# advanced.net
KiCad netlist of a schematic drawn in EAGLE
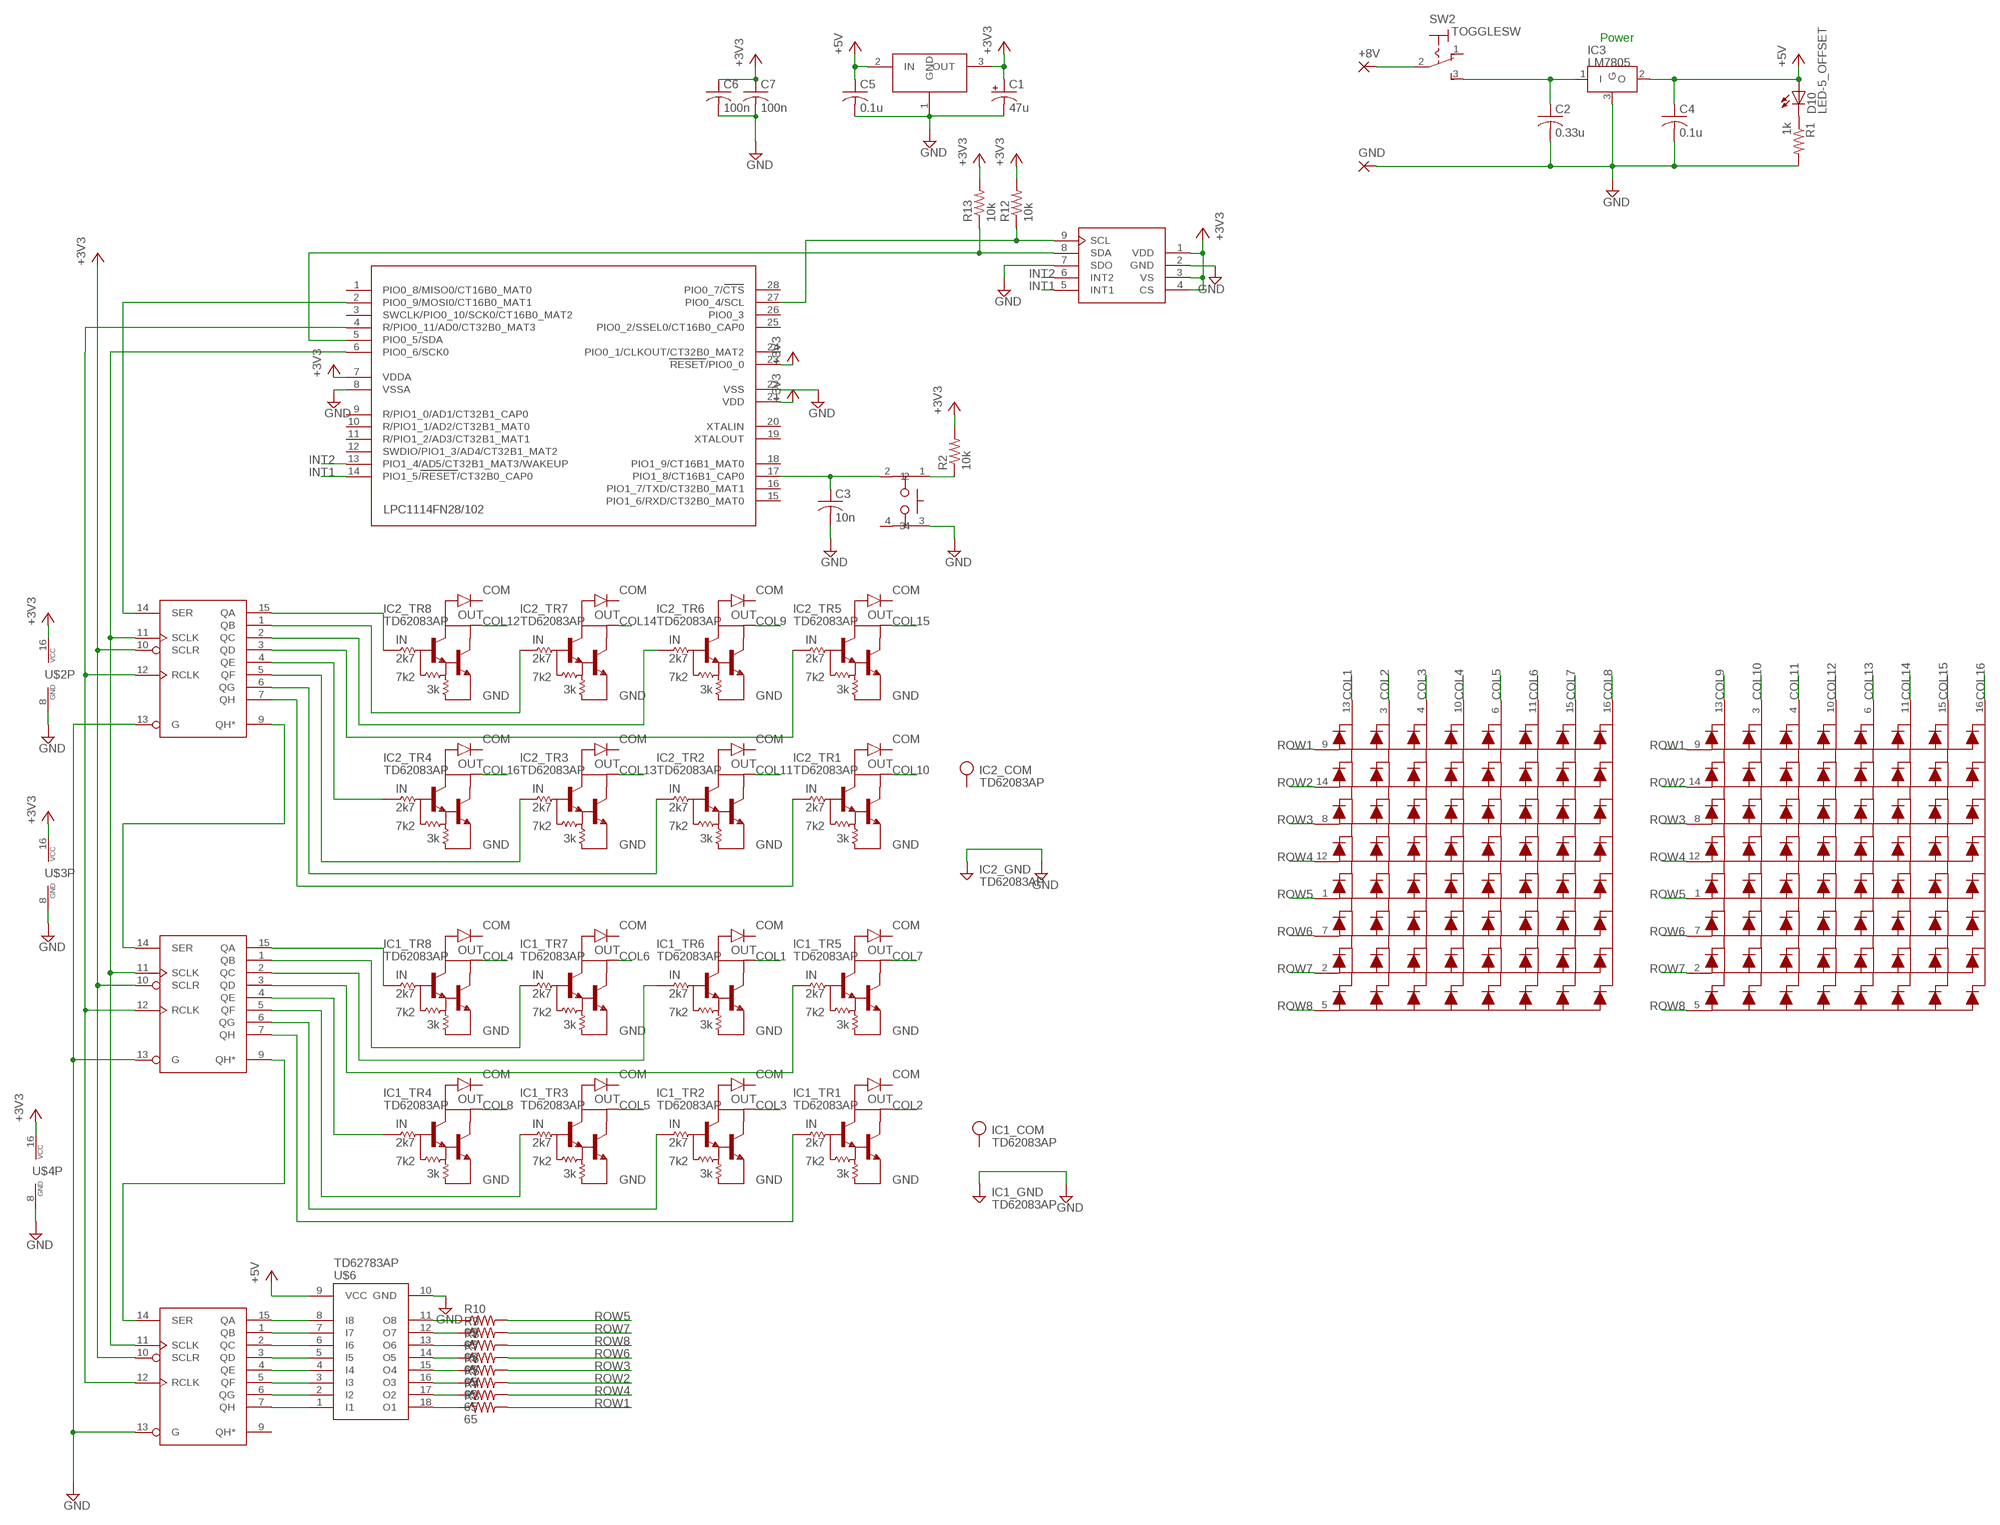
[diagram p0: schematic, sheet 1]

(export (version "E")
  (design (tool "Eeschema 10.0.6"))
  (components
    (comp (ref "+8V")
      (value "POWERPAD-2.0")
      (footprint "eagle-import:POWERPAD-2.0")
      (libsource (lib "eagle-import") (part "POWERPAD-2.0"))
    )
    (comp (ref "C1")
      (value "47u")
      (footprint "eagle-import:E2,5-5")
      (libsource (lib "eagle-import") (part "CC-2.5-5"))
    )
    (comp (ref "C2")
      (value "0.33u")
      (footprint "eagle-import:C025-024X044")
      (libsource (lib "eagle-import") (part "C/2.5"))
    )
    (comp (ref "C3")
      (value "10n")
      (footprint "eagle-import:C025-024X044")
      (libsource (lib "eagle-import") (part "C/2.5"))
    )
    (comp (ref "C4")
      (value "0.1u")
      (footprint "eagle-import:C025-024X044")
      (libsource (lib "eagle-import") (part "C/2.5"))
    )
    (comp (ref "C5")
      (value "0.1u")
      (footprint "eagle-import:C025-024X044")
      (libsource (lib "eagle-import") (part "C/2.5"))
    )
    (comp (ref "C6")
      (value "100n")
      (footprint "eagle-import:C025-024X044")
      (libsource (lib "eagle-import") (part "C/2.5"))
    )
    (comp (ref "C7")
      (value "100n")
      (footprint "eagle-import:C025-024X044")
      (libsource (lib "eagle-import") (part "C/2.5"))
    )
    (comp (ref "D1")
      (value "OSL641505-BX")
      (footprint "eagle-import:OSL641505-XX")
      (libsource (lib "eagle-import") (part "OSL641505-BX"))
    )
    (comp (ref "D10")
      (value "LED-5_OFFSET")
      (footprint "eagle-import:LED5_OFFSET")
      (libsource (lib "eagle-import") (part "LED-5_OFFSET"))
    )
    (comp (ref "DELDEL")
      (value "OSL641505-BX")
      (footprint "eagle-import:OSL641505-XX")
      (libsource (lib "eagle-import") (part "OSL641505-BX"))
    )
    (comp (ref "GND")
      (value "POWERPAD-2.0")
      (footprint "eagle-import:POWERPAD-2.0")
      (libsource (lib "eagle-import") (part "POWERPAD-2.0"))
    )
    (comp (ref "IC1")
      (value "TD62083AP")
      (footprint "eagle-import:DIL18")
      (libsource (lib "eagle-import") (part "TD62083AP"))
    )
    (comp (ref "IC2")
      (value "TD62083AP")
      (footprint "eagle-import:DIL18")
      (libsource (lib "eagle-import") (part "TD62083AP"))
    )
    (comp (ref "IC3")
      (value "LM7805")
      (footprint "eagle-import:7805-LARGEHOLE")
      (libsource (lib "eagle-import") (part "78(LARGEHOLE)"))
    )
    (comp (ref "R1")
      (value "1k")
      (footprint "eagle-import:0204_7")
      (libsource (lib "eagle-import") (part "R/7"))
    )
    (comp (ref "R2")
      (value "10k")
      (footprint "eagle-import:0204_7")
      (libsource (lib "eagle-import") (part "R/7"))
    )
    (comp (ref "R3")
      (value "65")
      (footprint "eagle-import:0204_7")
      (libsource (lib "eagle-import") (part "R/7"))
    )
    (comp (ref "R4")
      (value "65")
      (footprint "eagle-import:0204_7")
      (libsource (lib "eagle-import") (part "R/7"))
    )
    (comp (ref "R5")
      (value "65")
      (footprint "eagle-import:0204_7")
      (libsource (lib "eagle-import") (part "R/7"))
    )
    (comp (ref "R6")
      (value "65")
      (footprint "eagle-import:0204_7")
      (libsource (lib "eagle-import") (part "R/7"))
    )
    (comp (ref "R7")
      (value "65")
      (footprint "eagle-import:0204_7")
      (libsource (lib "eagle-import") (part "R/7"))
    )
    (comp (ref "R8")
      (value "65")
      (footprint "eagle-import:0204_7")
      (libsource (lib "eagle-import") (part "R/7"))
    )
    (comp (ref "R9")
      (value "65")
      (footprint "eagle-import:0204_7")
      (libsource (lib "eagle-import") (part "R/7"))
    )
    (comp (ref "R10")
      (value "65")
      (footprint "eagle-import:0204_7")
      (libsource (lib "eagle-import") (part "R/7"))
    )
    (comp (ref "R12")
      (value "10k")
      (footprint "eagle-import:0204_7")
      (libsource (lib "eagle-import") (part "R/7"))
    )
    (comp (ref "R13")
      (value "10k")
      (footprint "eagle-import:0204_7")
      (libsource (lib "eagle-import") (part "R/7"))
    )
    (comp (ref "SW1")
      (value "PUSHSW")
      (footprint "eagle-import:PUSHSW")
      (libsource (lib "eagle-import") (part "PUSHSW"))
    )
    (comp (ref "SW2")
      (value "TOGGLESW")
      (footprint "eagle-import:TOGGLESW")
      (libsource (lib "eagle-import") (part "TOGGLESW"))
    )
    (comp (ref "U$1")
      (value "LPC1114FN28")
      (footprint "eagle-import:DIP28(600MIL)")
      (libsource (lib "eagle-import") (part "LPC1114FN28"))
    )
    (comp (ref "U$2")
      (value "74HC595N")
      (footprint "eagle-import:DIL16")
      (libsource (lib "eagle-import") (part "74595NHC"))
    )
    (comp (ref "U$3")
      (value "74HC595N")
      (footprint "eagle-import:DIL16")
      (libsource (lib "eagle-import") (part "74595NHC"))
    )
    (comp (ref "U$4")
      (value "74HC595N")
      (footprint "eagle-import:DIL16")
      (libsource (lib "eagle-import") (part "74595NHC"))
    )
    (comp (ref "U$5")
      (value "AKI_ADXL345")
      (footprint "eagle-import:AKI_ADXL345")
      (libsource (lib "eagle-import") (part "AKI_ADXL345"))
    )
    (comp (ref "U$6")
      (value "TD62783AP")
      (footprint "eagle-import:DIL18")
      (libsource (lib "eagle-import") (part "TD62783AP"))
    )
    (comp (ref "U$8")
      (value "S-812C3.3AY")
      (footprint "eagle-import:TO92-")
      (libsource (lib "eagle-import") (part "S-812CAY3.3"))
    )
  )
  (nets
    (net (code "1") (name "+3V3") (class "Default")
      (node (ref "C1") (pin "+") (pinfunction "+_+") (pintype "passive"))
      (node (ref "C6") (pin "1") (pinfunction "1_1") (pintype "passive"))
      (node (ref "C7") (pin "1") (pinfunction "1_1") (pintype "passive"))
      (node (ref "R12") (pin "2") (pinfunction "2_2") (pintype "passive"))
      (node (ref "R13") (pin "2") (pinfunction "2_2") (pintype "passive"))
      (node (ref "R2") (pin "2") (pinfunction "2_2") (pintype "passive"))
      (node (ref "U$1") (pin "21") (pinfunction "VDD_21") (pintype "power_in"))
      (node (ref "U$1") (pin "23") (pinfunction "RESET/PIO0_0_23") (pintype "bidirectional"))
      (node (ref "U$1") (pin "7") (pinfunction "VDDA_7") (pintype "power_in"))
      (node (ref "U$2") (pin "10") (pinfunction "SCLR_10") (pintype "input"))
      (node (ref "U$2") (pin "16") (pinfunction "VCC_16") (pintype "power_in"))
      (node (ref "U$3") (pin "10") (pinfunction "SCLR_10") (pintype "input"))
      (node (ref "U$3") (pin "16") (pinfunction "VCC_16") (pintype "power_in"))
      (node (ref "U$4") (pin "10") (pinfunction "SCLR_10") (pintype "input"))
      (node (ref "U$4") (pin "16") (pinfunction "VCC_16") (pintype "power_in"))
      (node (ref "U$5") (pin "1") (pinfunction "VDD_1") (pintype "power_in"))
      (node (ref "U$5") (pin "3") (pinfunction "VS_3") (pintype "power_in"))
      (node (ref "U$5") (pin "4") (pinfunction "CS_4") (pintype "input"))
      (node (ref "U$8") (pin "3") (pinfunction "OUT_3") (pintype "power_in"))
    )
    (net (code "2") (name "+5V") (class "Default")
      (node (ref "C4") (pin "1") (pinfunction "1_1") (pintype "passive"))
      (node (ref "C5") (pin "1") (pinfunction "1_1") (pintype "passive"))
      (node (ref "D10") (pin "A") (pinfunction "A_A") (pintype "passive"))
      (node (ref "IC3") (pin "2") (pinfunction "O_2") (pintype "power_in"))
      (node (ref "U$6") (pin "9") (pinfunction "VCC_9") (pintype "power_in"))
      (node (ref "U$8") (pin "2") (pinfunction "IN_2") (pintype "power_in"))
    )
    (net (code "3") (name "/COL1") (class "Default")
      (node (ref "D1") (pin "13") (pinfunction "P$9_13") (pintype "passive"))
      (node (ref "IC1") (pin "13") (pinfunction "C_13") (pintype "passive"))
    )
    (net (code "4") (name "/COL2") (class "Default")
      (node (ref "D1") (pin "3") (pinfunction "P$10_3") (pintype "passive"))
      (node (ref "IC1") (pin "18") (pinfunction "C_18") (pintype "passive"))
    )
    (net (code "5") (name "/COL3") (class "Default")
      (node (ref "D1") (pin "4") (pinfunction "P$11_4") (pintype "passive"))
      (node (ref "IC1") (pin "17") (pinfunction "C_17") (pintype "passive"))
    )
    (net (code "6") (name "/COL4") (class "Default")
      (node (ref "D1") (pin "10") (pinfunction "P$12_10") (pintype "passive"))
      (node (ref "IC1") (pin "11") (pinfunction "C_11") (pintype "passive"))
    )
    (net (code "7") (name "/COL5") (class "Default")
      (node (ref "D1") (pin "6") (pinfunction "P$13_6") (pintype "passive"))
      (node (ref "IC1") (pin "16") (pinfunction "C_16") (pintype "passive"))
    )
    (net (code "8") (name "/COL6") (class "Default")
      (node (ref "D1") (pin "11") (pinfunction "P$14_11") (pintype "passive"))
      (node (ref "IC1") (pin "12") (pinfunction "C_12") (pintype "passive"))
    )
    (net (code "9") (name "/COL7") (class "Default")
      (node (ref "D1") (pin "15") (pinfunction "P$15_15") (pintype "passive"))
      (node (ref "IC1") (pin "14") (pinfunction "C_14") (pintype "passive"))
    )
    (net (code "10") (name "/COL8") (class "Default")
      (node (ref "D1") (pin "16") (pinfunction "P$16_16") (pintype "passive"))
      (node (ref "IC1") (pin "15") (pinfunction "C_15") (pintype "passive"))
    )
    (net (code "11") (name "/COL9") (class "Default")
      (node (ref "DELDEL") (pin "13") (pinfunction "P$9_13") (pintype "passive"))
      (node (ref "IC2") (pin "13") (pinfunction "C_13") (pintype "passive"))
    )
    (net (code "12") (name "/COL10") (class "Default")
      (node (ref "DELDEL") (pin "3") (pinfunction "P$10_3") (pintype "passive"))
      (node (ref "IC2") (pin "18") (pinfunction "C_18") (pintype "passive"))
    )
    (net (code "13") (name "/COL11") (class "Default")
      (node (ref "DELDEL") (pin "4") (pinfunction "P$11_4") (pintype "passive"))
      (node (ref "IC2") (pin "17") (pinfunction "C_17") (pintype "passive"))
    )
    (net (code "14") (name "/COL12") (class "Default")
      (node (ref "DELDEL") (pin "10") (pinfunction "P$12_10") (pintype "passive"))
      (node (ref "IC2") (pin "11") (pinfunction "C_11") (pintype "passive"))
    )
    (net (code "15") (name "/COL13") (class "Default")
      (node (ref "DELDEL") (pin "6") (pinfunction "P$13_6") (pintype "passive"))
      (node (ref "IC2") (pin "16") (pinfunction "C_16") (pintype "passive"))
    )
    (net (code "16") (name "/COL14") (class "Default")
      (node (ref "DELDEL") (pin "11") (pinfunction "P$14_11") (pintype "passive"))
      (node (ref "IC2") (pin "12") (pinfunction "C_12") (pintype "passive"))
    )
    (net (code "17") (name "/COL15") (class "Default")
      (node (ref "DELDEL") (pin "15") (pinfunction "P$15_15") (pintype "passive"))
      (node (ref "IC2") (pin "14") (pinfunction "C_14") (pintype "passive"))
    )
    (net (code "18") (name "/COL16") (class "Default")
      (node (ref "DELDEL") (pin "16") (pinfunction "P$16_16") (pintype "passive"))
      (node (ref "IC2") (pin "15") (pinfunction "C_15") (pintype "passive"))
    )
    (net (code "19") (name "/INT1") (class "Default")
      (node (ref "U$1") (pin "14") (pinfunction "PIO1_5/RESET/CT32B0_CAP0_14") (pintype "bidirectional"))
      (node (ref "U$5") (pin "5") (pinfunction "INT1_5") (pintype "output"))
    )
    (net (code "20") (name "/INT2") (class "Default")
      (node (ref "U$1") (pin "13") (pinfunction "PIO1_4/AD5/CT32B1_MAT3/WAKEUP_13") (pintype "bidirectional"))
      (node (ref "U$5") (pin "6") (pinfunction "INT2_6") (pintype "output"))
    )
    (net (code "21") (name "/ROW1") (class "Default")
      (node (ref "D1") (pin "9") (pinfunction "P$1_9") (pintype "passive"))
      (node (ref "DELDEL") (pin "9") (pinfunction "P$1_9") (pintype "passive"))
      (node (ref "R3") (pin "2") (pinfunction "2_2") (pintype "passive"))
    )
    (net (code "22") (name "/ROW2") (class "Default")
      (node (ref "D1") (pin "14") (pinfunction "P$2_14") (pintype "passive"))
      (node (ref "DELDEL") (pin "14") (pinfunction "P$2_14") (pintype "passive"))
      (node (ref "R5") (pin "2") (pinfunction "2_2") (pintype "passive"))
    )
    (net (code "23") (name "/ROW3") (class "Default")
      (node (ref "D1") (pin "8") (pinfunction "P$3_8") (pintype "passive"))
      (node (ref "DELDEL") (pin "8") (pinfunction "P$3_8") (pintype "passive"))
      (node (ref "R6") (pin "2") (pinfunction "2_2") (pintype "passive"))
    )
    (net (code "24") (name "/ROW4") (class "Default")
      (node (ref "D1") (pin "12") (pinfunction "P$4_12") (pintype "passive"))
      (node (ref "DELDEL") (pin "12") (pinfunction "P$4_12") (pintype "passive"))
      (node (ref "R4") (pin "2") (pinfunction "2_2") (pintype "passive"))
    )
    (net (code "25") (name "/ROW5") (class "Default")
      (node (ref "D1") (pin "1") (pinfunction "P$5_1") (pintype "passive"))
      (node (ref "DELDEL") (pin "1") (pinfunction "P$5_1") (pintype "passive"))
      (node (ref "R10") (pin "2") (pinfunction "2_2") (pintype "passive"))
    )
    (net (code "26") (name "/ROW6") (class "Default")
      (node (ref "D1") (pin "7") (pinfunction "P$6_7") (pintype "passive"))
      (node (ref "DELDEL") (pin "7") (pinfunction "P$6_7") (pintype "passive"))
      (node (ref "R7") (pin "2") (pinfunction "2_2") (pintype "passive"))
    )
    (net (code "27") (name "/ROW7") (class "Default")
      (node (ref "D1") (pin "2") (pinfunction "P$7_2") (pintype "passive"))
      (node (ref "DELDEL") (pin "2") (pinfunction "P$7_2") (pintype "passive"))
      (node (ref "R9") (pin "2") (pinfunction "2_2") (pintype "passive"))
    )
    (net (code "28") (name "/ROW8") (class "Default")
      (node (ref "D1") (pin "5") (pinfunction "P$8_5") (pintype "passive"))
      (node (ref "DELDEL") (pin "5") (pinfunction "P$8_5") (pintype "passive"))
      (node (ref "R8") (pin "2") (pinfunction "2_2") (pintype "passive"))
    )
    (net (code "29") (name "GND") (class "Default")
      (node (ref "C1") (pin "-") (pinfunction "-_-") (pintype "passive"))
      (node (ref "C2") (pin "2") (pinfunction "2_2") (pintype "passive"))
      (node (ref "C3") (pin "2") (pinfunction "2_2") (pintype "passive"))
      (node (ref "C4") (pin "2") (pinfunction "2_2") (pintype "passive"))
      (node (ref "C5") (pin "2") (pinfunction "2_2") (pintype "passive"))
      (node (ref "C6") (pin "2") (pinfunction "2_2") (pintype "passive"))
      (node (ref "C7") (pin "2") (pinfunction "2_2") (pintype "passive"))
      (node (ref "GND") (pin "1") (pinfunction "P_1") (pintype "passive"))
      (node (ref "IC1") (pin "9") (pinfunction "GND_9") (pintype "power_in"))
      (node (ref "IC2") (pin "9") (pinfunction "GND_9") (pintype "power_in"))
      (node (ref "IC3") (pin "3") (pinfunction "G_3") (pintype "power_in"))
      (node (ref "R1") (pin "2") (pinfunction "2_2") (pintype "passive"))
      (node (ref "SW1") (pin "3") (pinfunction "3_3") (pintype "bidirectional"))
      (node (ref "U$1") (pin "22") (pinfunction "VSS_22") (pintype "power_in"))
      (node (ref "U$1") (pin "8") (pinfunction "VSSA_8") (pintype "power_in"))
      (node (ref "U$2") (pin "13") (pinfunction "G_13") (pintype "input"))
      (node (ref "U$2") (pin "8") (pinfunction "GND_8") (pintype "power_in"))
      (node (ref "U$3") (pin "13") (pinfunction "G_13") (pintype "input"))
      (node (ref "U$3") (pin "8") (pinfunction "GND_8") (pintype "power_in"))
      (node (ref "U$4") (pin "13") (pinfunction "G_13") (pintype "input"))
      (node (ref "U$4") (pin "8") (pinfunction "GND_8") (pintype "power_in"))
      (node (ref "U$5") (pin "2") (pinfunction "GND_2") (pintype "power_in"))
      (node (ref "U$5") (pin "7") (pinfunction "SDO_7") (pintype "bidirectional"))
      (node (ref "U$6") (pin "10") (pinfunction "GND_10") (pintype "power_in"))
      (node (ref "U$8") (pin "1") (pinfunction "GND_1") (pintype "power_in"))
    )
    (net (code "30") (name "Net-(+8V-P)") (class "Default")
      (node (ref "+8V") (pin "1") (pinfunction "P_1") (pintype "passive"))
      (node (ref "SW2") (pin "2") (pinfunction "P_2") (pintype "passive"))
    )
    (net (code "31") (name "Net-(D10-PadK)") (class "Default")
      (node (ref "D10") (pin "K") (pinfunction "K_K") (pintype "passive"))
      (node (ref "R1") (pin "1") (pinfunction "1_1") (pintype "passive"))
    )
    (net (code "32") (name "Net-(IC1C-B)") (class "Default")
      (node (ref "IC1") (pin "1") (pinfunction "B_1") (pintype "passive"))
      (node (ref "U$3") (pin "7") (pinfunction "QH_7") (pintype "output"))
    )
    (net (code "33") (name "Net-(IC1D-B)") (class "Default")
      (node (ref "IC1") (pin "2") (pinfunction "B_2") (pintype "passive"))
      (node (ref "U$3") (pin "6") (pinfunction "QG_6") (pintype "output"))
    )
    (net (code "34") (name "Net-(IC1E-B)") (class "Default")
      (node (ref "IC1") (pin "3") (pinfunction "B_3") (pintype "passive"))
      (node (ref "U$3") (pin "5") (pinfunction "QF_5") (pintype "output"))
    )
    (net (code "35") (name "Net-(IC1F-B)") (class "Default")
      (node (ref "IC1") (pin "4") (pinfunction "B_4") (pintype "passive"))
      (node (ref "U$3") (pin "4") (pinfunction "QE_4") (pintype "output"))
    )
    (net (code "36") (name "Net-(IC1G-B)") (class "Default")
      (node (ref "IC1") (pin "5") (pinfunction "B_5") (pintype "passive"))
      (node (ref "U$3") (pin "3") (pinfunction "QD_3") (pintype "output"))
    )
    (net (code "37") (name "Net-(IC1H-B)") (class "Default")
      (node (ref "IC1") (pin "6") (pinfunction "B_6") (pintype "passive"))
      (node (ref "U$3") (pin "2") (pinfunction "QC_2") (pintype "output"))
    )
    (net (code "38") (name "Net-(IC1I-B)") (class "Default")
      (node (ref "IC1") (pin "7") (pinfunction "B_7") (pintype "passive"))
      (node (ref "U$3") (pin "1") (pinfunction "QB_1") (pintype "output"))
    )
    (net (code "39") (name "Net-(IC1J-B)") (class "Default")
      (node (ref "IC1") (pin "8") (pinfunction "B_8") (pintype "passive"))
      (node (ref "U$3") (pin "15") (pinfunction "QA_15") (pintype "output"))
    )
    (net (code "40") (name "Net-(IC2C-B)") (class "Default")
      (node (ref "IC2") (pin "1") (pinfunction "B_1") (pintype "passive"))
      (node (ref "U$4") (pin "7") (pinfunction "QH_7") (pintype "output"))
    )
    (net (code "41") (name "Net-(IC2D-B)") (class "Default")
      (node (ref "IC2") (pin "2") (pinfunction "B_2") (pintype "passive"))
      (node (ref "U$4") (pin "6") (pinfunction "QG_6") (pintype "output"))
    )
    (net (code "42") (name "Net-(IC2E-B)") (class "Default")
      (node (ref "IC2") (pin "3") (pinfunction "B_3") (pintype "passive"))
      (node (ref "U$4") (pin "5") (pinfunction "QF_5") (pintype "output"))
    )
    (net (code "43") (name "Net-(IC2F-B)") (class "Default")
      (node (ref "IC2") (pin "4") (pinfunction "B_4") (pintype "passive"))
      (node (ref "U$4") (pin "4") (pinfunction "QE_4") (pintype "output"))
    )
    (net (code "44") (name "Net-(IC2G-B)") (class "Default")
      (node (ref "IC2") (pin "5") (pinfunction "B_5") (pintype "passive"))
      (node (ref "U$4") (pin "3") (pinfunction "QD_3") (pintype "output"))
    )
    (net (code "45") (name "Net-(IC2H-B)") (class "Default")
      (node (ref "IC2") (pin "6") (pinfunction "B_6") (pintype "passive"))
      (node (ref "U$4") (pin "2") (pinfunction "QC_2") (pintype "output"))
    )
    (net (code "46") (name "Net-(IC2I-B)") (class "Default")
      (node (ref "IC2") (pin "7") (pinfunction "B_7") (pintype "passive"))
      (node (ref "U$4") (pin "1") (pinfunction "QB_1") (pintype "output"))
    )
    (net (code "47") (name "Net-(IC2J-B)") (class "Default")
      (node (ref "IC2") (pin "8") (pinfunction "B_8") (pintype "passive"))
      (node (ref "U$4") (pin "15") (pinfunction "QA_15") (pintype "output"))
    )
    (net (code "48") (name "Net-(IC3-I)") (class "Default")
      (node (ref "C2") (pin "1") (pinfunction "1_1") (pintype "passive"))
      (node (ref "IC3") (pin "1") (pinfunction "I_1") (pintype "power_in"))
      (node (ref "SW2") (pin "3") (pinfunction "S_3") (pintype "passive"))
    )
    (net (code "49") (name "Net-(R2-Pad1)") (class "Default")
      (node (ref "R2") (pin "1") (pinfunction "1_1") (pintype "passive"))
      (node (ref "SW1") (pin "1") (pinfunction "1_1") (pintype "bidirectional"))
    )
    (net (code "50") (name "Net-(U$1-PIO0_4{slash}SCL)") (class "Default")
      (node (ref "R12") (pin "1") (pinfunction "1_1") (pintype "passive"))
      (node (ref "U$1") (pin "27") (pinfunction "PIO0_4/SCL_27") (pintype "bidirectional"))
      (node (ref "U$5") (pin "9") (pinfunction "SCL_9") (pintype "input"))
    )
    (net (code "51") (name "Net-(U$1-PIO0_5{slash}SDA)") (class "Default")
      (node (ref "R13") (pin "1") (pinfunction "1_1") (pintype "passive"))
      (node (ref "U$1") (pin "5") (pinfunction "PIO0_5/SDA_5") (pintype "bidirectional"))
      (node (ref "U$5") (pin "8") (pinfunction "SDA_8") (pintype "bidirectional"))
    )
    (net (code "52") (name "Net-(U$1-PIO0_6{slash}SCK0)") (class "Default")
      (node (ref "U$1") (pin "6") (pinfunction "PIO0_6/SCK0_6") (pintype "bidirectional"))
      (node (ref "U$2") (pin "11") (pinfunction "SCLK_11") (pintype "input"))
      (node (ref "U$3") (pin "11") (pinfunction "SCLK_11") (pintype "input"))
      (node (ref "U$4") (pin "11") (pinfunction "SCLK_11") (pintype "input"))
    )
    (net (code "53") (name "Net-(U$1-PIO0_9{slash}MOSI0{slash}CT16B0_MAT1)") (class "Default")
      (node (ref "U$1") (pin "2") (pinfunction "PIO0_9/MOSI0/CT16B0_MAT1_2") (pintype "bidirectional"))
      (node (ref "U$4") (pin "14") (pinfunction "SER_14") (pintype "input"))
    )
    (net (code "54") (name "Net-(U$1-PIO1_8{slash}CT16B1_CAP0)") (class "Default")
      (node (ref "C3") (pin "1") (pinfunction "1_1") (pintype "passive"))
      (node (ref "SW1") (pin "2") (pinfunction "2_2") (pintype "bidirectional"))
      (node (ref "U$1") (pin "17") (pinfunction "PIO1_8/CT16B1_CAP0_17") (pintype "bidirectional"))
    )
    (net (code "55") (name "Net-(U$1-R{slash}PIO0_11{slash}AD0{slash}CT32B0_MAT3)") (class "Default")
      (node (ref "U$1") (pin "4") (pinfunction "R/PIO0_11/AD0/CT32B0_MAT3_4") (pintype "bidirectional"))
      (node (ref "U$2") (pin "12") (pinfunction "RCLK_12") (pintype "input"))
      (node (ref "U$3") (pin "12") (pinfunction "RCLK_12") (pintype "input"))
      (node (ref "U$4") (pin "12") (pinfunction "RCLK_12") (pintype "input"))
    )
    (net (code "56") (name "Net-(U$2A-QA)") (class "Default")
      (node (ref "U$2") (pin "15") (pinfunction "QA_15") (pintype "output"))
      (node (ref "U$6") (pin "8") (pinfunction "I8_8") (pintype "input"))
    )
    (net (code "57") (name "Net-(U$2A-QB)") (class "Default")
      (node (ref "U$2") (pin "1") (pinfunction "QB_1") (pintype "output"))
      (node (ref "U$6") (pin "7") (pinfunction "I7_7") (pintype "input"))
    )
    (net (code "58") (name "Net-(U$2A-QC)") (class "Default")
      (node (ref "U$2") (pin "2") (pinfunction "QC_2") (pintype "output"))
      (node (ref "U$6") (pin "6") (pinfunction "I6_6") (pintype "input"))
    )
    (net (code "59") (name "Net-(U$2A-QD)") (class "Default")
      (node (ref "U$2") (pin "3") (pinfunction "QD_3") (pintype "output"))
      (node (ref "U$6") (pin "5") (pinfunction "I5_5") (pintype "input"))
    )
    (net (code "60") (name "Net-(U$2A-QE)") (class "Default")
      (node (ref "U$2") (pin "4") (pinfunction "QE_4") (pintype "output"))
      (node (ref "U$6") (pin "4") (pinfunction "I4_4") (pintype "input"))
    )
    (net (code "61") (name "Net-(U$2A-QF)") (class "Default")
      (node (ref "U$2") (pin "5") (pinfunction "QF_5") (pintype "output"))
      (node (ref "U$6") (pin "3") (pinfunction "I3_3") (pintype "input"))
    )
    (net (code "62") (name "Net-(U$2A-QG)") (class "Default")
      (node (ref "U$2") (pin "6") (pinfunction "QG_6") (pintype "output"))
      (node (ref "U$6") (pin "2") (pinfunction "I2_2") (pintype "input"))
    )
    (net (code "63") (name "Net-(U$2A-QH)") (class "Default")
      (node (ref "U$2") (pin "7") (pinfunction "QH_7") (pintype "output"))
      (node (ref "U$6") (pin "1") (pinfunction "I1_1") (pintype "input"))
    )
    (net (code "64") (name "Net-(U$2A-SER)") (class "Default")
      (node (ref "U$2") (pin "14") (pinfunction "SER_14") (pintype "input"))
      (node (ref "U$3") (pin "9") (pinfunction "QH*_9") (pintype "output"))
    )
    (net (code "65") (name "Net-(U$3A-SER)") (class "Default")
      (node (ref "U$3") (pin "14") (pinfunction "SER_14") (pintype "input"))
      (node (ref "U$4") (pin "9") (pinfunction "QH*_9") (pintype "output"))
    )
    (net (code "66") (name "Net-(U$6-O1)") (class "Default")
      (node (ref "R3") (pin "1") (pinfunction "1_1") (pintype "passive"))
      (node (ref "U$6") (pin "18") (pinfunction "O1_18") (pintype "output"))
    )
    (net (code "67") (name "Net-(U$6-O2)") (class "Default")
      (node (ref "R4") (pin "1") (pinfunction "1_1") (pintype "passive"))
      (node (ref "U$6") (pin "17") (pinfunction "O2_17") (pintype "output"))
    )
    (net (code "68") (name "Net-(U$6-O3)") (class "Default")
      (node (ref "R5") (pin "1") (pinfunction "1_1") (pintype "passive"))
      (node (ref "U$6") (pin "16") (pinfunction "O3_16") (pintype "output"))
    )
    (net (code "69") (name "Net-(U$6-O4)") (class "Default")
      (node (ref "R6") (pin "1") (pinfunction "1_1") (pintype "passive"))
      (node (ref "U$6") (pin "15") (pinfunction "O4_15") (pintype "output"))
    )
    (net (code "70") (name "Net-(U$6-O5)") (class "Default")
      (node (ref "R7") (pin "1") (pinfunction "1_1") (pintype "passive"))
      (node (ref "U$6") (pin "14") (pinfunction "O5_14") (pintype "output"))
    )
    (net (code "71") (name "Net-(U$6-O6)") (class "Default")
      (node (ref "R8") (pin "1") (pinfunction "1_1") (pintype "passive"))
      (node (ref "U$6") (pin "13") (pinfunction "O6_13") (pintype "output"))
    )
    (net (code "72") (name "Net-(U$6-O7)") (class "Default")
      (node (ref "R9") (pin "1") (pinfunction "1_1") (pintype "passive"))
      (node (ref "U$6") (pin "12") (pinfunction "O7_12") (pintype "output"))
    )
    (net (code "73") (name "Net-(U$6-O8)") (class "Default")
      (node (ref "R10") (pin "1") (pinfunction "1_1") (pintype "passive"))
      (node (ref "U$6") (pin "11") (pinfunction "O8_11") (pintype "output"))
    )
    (net (code "74") (name "unconnected-(IC1A-P$1-Pad10)") (class "Default")
      (node (ref "IC1") (pin "10") (pinfunction "P$1_10") (pintype "bidirectional"))
    )
    (net (code "75") (name "unconnected-(IC2A-P$1-Pad10)") (class "Default")
      (node (ref "IC2") (pin "10") (pinfunction "P$1_10") (pintype "bidirectional"))
    )
    (net (code "76") (name "unconnected-(SW1-Pad4)") (class "Default")
      (node (ref "SW1") (pin "4") (pinfunction "4_4") (pintype "bidirectional"))
    )
    (net (code "77") (name "unconnected-(SW2A-O-Pad1)") (class "Default")
      (node (ref "SW2") (pin "1") (pinfunction "O_1") (pintype "passive"))
    )
    (net (code "78") (name "unconnected-(U$1-PIO0_1{slash}CLKOUT{slash}CT32B0_MAT2-Pad24)") (class "Default")
      (node (ref "U$1") (pin "24") (pinfunction "PIO0_1/CLKOUT/CT32B0_MAT2_24") (pintype "bidirectional"))
    )
    (net (code "79") (name "unconnected-(U$1-PIO0_2{slash}SSEL0{slash}CT16B0_CAP0-Pad25)") (class "Default")
      (node (ref "U$1") (pin "25") (pinfunction "PIO0_2/SSEL0/CT16B0_CAP0_25") (pintype "bidirectional"))
    )
    (net (code "80") (name "unconnected-(U$1-PIO0_3-Pad26)") (class "Default")
      (node (ref "U$1") (pin "26") (pinfunction "PIO0_3_26") (pintype "bidirectional"))
    )
    (net (code "81") (name "unconnected-(U$1-PIO0_7{slash}CTS-Pad28)") (class "Default")
      (node (ref "U$1") (pin "28") (pinfunction "PIO0_7/CTS_28") (pintype "bidirectional"))
    )
    (net (code "82") (name "unconnected-(U$1-PIO0_8{slash}MISO0{slash}CT16B0_MAT0-Pad1)") (class "Default")
      (node (ref "U$1") (pin "1") (pinfunction "PIO0_8/MISO0/CT16B0_MAT0_1") (pintype "bidirectional"))
    )
    (net (code "83") (name "unconnected-(U$1-PIO1_6{slash}RXD{slash}CT32B0_MAT0-Pad15)") (class "Default")
      (node (ref "U$1") (pin "15") (pinfunction "PIO1_6/RXD/CT32B0_MAT0_15") (pintype "bidirectional"))
    )
    (net (code "84") (name "unconnected-(U$1-PIO1_7{slash}TXD{slash}CT32B0_MAT1-Pad16)") (class "Default")
      (node (ref "U$1") (pin "16") (pinfunction "PIO1_7/TXD/CT32B0_MAT1_16") (pintype "bidirectional"))
    )
    (net (code "85") (name "unconnected-(U$1-PIO1_9{slash}CT16B1_MAT0-Pad18)") (class "Default")
      (node (ref "U$1") (pin "18") (pinfunction "PIO1_9/CT16B1_MAT0_18") (pintype "bidirectional"))
    )
    (net (code "86") (name "unconnected-(U$1-R{slash}PIO1_0{slash}AD1{slash}CT32B1_CAP0-Pad9)") (class "Default")
      (node (ref "U$1") (pin "9") (pinfunction "R/PIO1_0/AD1/CT32B1_CAP0_9") (pintype "bidirectional"))
    )
    (net (code "87") (name "unconnected-(U$1-R{slash}PIO1_1{slash}AD2{slash}CT32B1_MAT0-Pad10)") (class "Default")
      (node (ref "U$1") (pin "10") (pinfunction "R/PIO1_1/AD2/CT32B1_MAT0_10") (pintype "bidirectional"))
    )
    (net (code "88") (name "unconnected-(U$1-R{slash}PIO1_2{slash}AD3{slash}CT32B1_MAT1-Pad11)") (class "Default")
      (node (ref "U$1") (pin "11") (pinfunction "R/PIO1_2/AD3/CT32B1_MAT1_11") (pintype "bidirectional"))
    )
    (net (code "89") (name "unconnected-(U$1-SWCLK{slash}PIO0_10{slash}SCK0{slash}CT16B0_MAT2-Pad3)") (class "Default")
      (node (ref "U$1") (pin "3") (pinfunction "SWCLK/PIO0_10/SCK0/CT16B0_MAT2_3") (pintype "bidirectional"))
    )
    (net (code "90") (name "unconnected-(U$1-SWDIO{slash}PIO1_3{slash}AD4{slash}CT32B1_MAT2-Pad12)") (class "Default")
      (node (ref "U$1") (pin "12") (pinfunction "SWDIO/PIO1_3/AD4/CT32B1_MAT2_12") (pintype "bidirectional"))
    )
    (net (code "91") (name "unconnected-(U$1-XTALIN-Pad20)") (class "Default")
      (node (ref "U$1") (pin "20") (pinfunction "XTALIN_20") (pintype "bidirectional"))
    )
    (net (code "92") (name "unconnected-(U$1-XTALOUT-Pad19)") (class "Default")
      (node (ref "U$1") (pin "19") (pinfunction "XTALOUT_19") (pintype "bidirectional"))
    )
    (net (code "93") (name "unconnected-(U$2A-QH*-Pad9)") (class "Default")
      (node (ref "U$2") (pin "9") (pinfunction "QH*_9") (pintype "output"))
    )
  )
)
